# PWR.net
KiCad netlist of a schematic drawn in Altium Designer
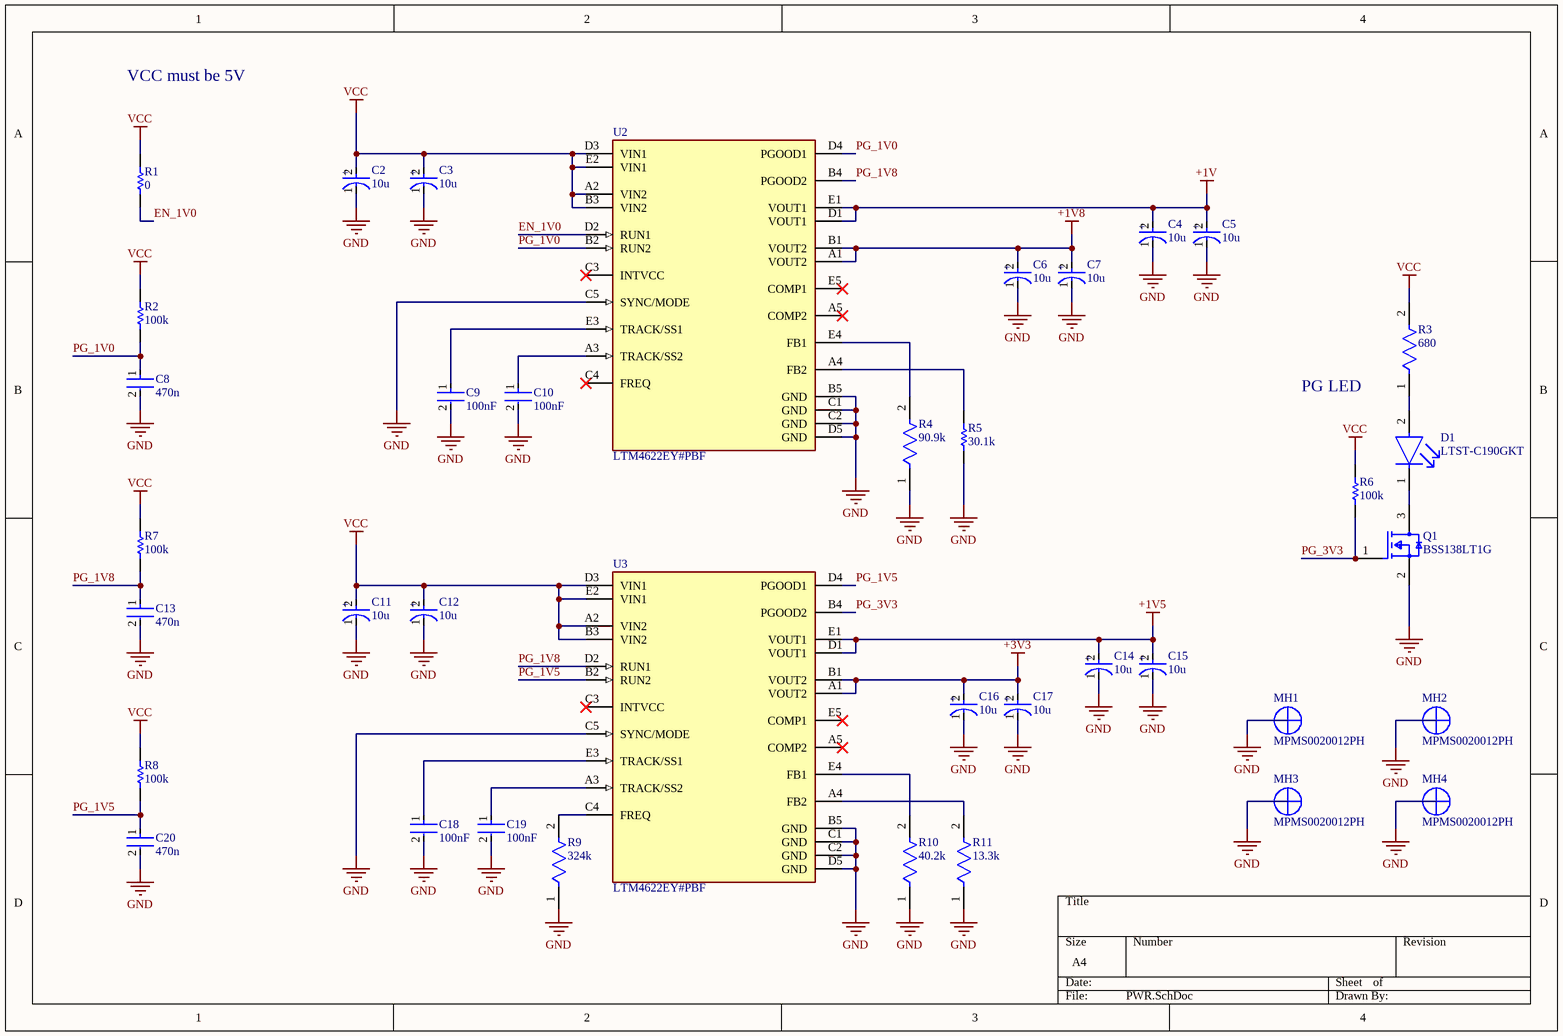
[diagram p0: PWR.SchDoc]

(export (version "E")
  (design (tool "Eeschema 10.0.6"))
  (components
    (comp (ref "C2")
      (value "10u")
      (footprint "FP-TAJB-MFG")
      (description "10uF 25V  ±10% 2.5Ω 1210  SMD Tantalum Capacitor")
      (fields (field (name "TOLERANCE") "10%"))
      (libsource (lib "Altium Content Vault") (part "203bc49f2ac43e59fd269a8c329ed05"))
    )
    (comp (ref "C3")
      (value "10u")
      (footprint "FP-TAJB-MFG")
      (description "10uF 25V  ±10% 2.5Ω 1210  SMD Tantalum Capacitor")
      (fields (field (name "TOLERANCE") "10%"))
      (libsource (lib "Altium Content Vault") (part "203bc49f2ac43e59fd269a8c329ed05"))
    )
    (comp (ref "C4")
      (value "10u")
      (footprint "FP-TAJA-MFG")
      (description "10uF 10V  ±10% 3Ω 1206  SMD Tantalum Capacitor")
      (fields (field (name "TOLERANCE") "10%") (field (name "VOLTAGE") "10V"))
      (libsource (lib "Altium Content Vault") (part "203bc49f2ac43e59fd269a8c329ed05"))
    )
    (comp (ref "C5")
      (value "10u")
      (footprint "FP-TAJA-MFG")
      (description "10uF 10V  ±10% 3Ω 1206  SMD Tantalum Capacitor")
      (fields (field (name "TOLERANCE") "10%") (field (name "VOLTAGE") "10V"))
      (libsource (lib "Altium Content Vault") (part "203bc49f2ac43e59fd269a8c329ed05"))
    )
    (comp (ref "C6")
      (value "10u")
      (footprint "FP-TAJA-MFG")
      (description "10uF 10V  ±10% 3Ω 1206  SMD Tantalum Capacitor")
      (fields (field (name "TOLERANCE") "10%") (field (name "VOLTAGE") "10V"))
      (libsource (lib "Altium Content Vault") (part "203bc49f2ac43e59fd269a8c329ed05"))
    )
    (comp (ref "C7")
      (value "10u")
      (footprint "FP-TAJA-MFG")
      (description "10uF 10V  ±10% 3Ω 1206  SMD Tantalum Capacitor")
      (fields (field (name "TOLERANCE") "10%") (field (name "VOLTAGE") "10V"))
      (libsource (lib "Altium Content Vault") (part "203bc49f2ac43e59fd269a8c329ed05"))
    )
    (comp (ref "C8")
      (value "470n")
      (footprint "FP-C0603C-CF-MFG")
      (description "CAP CER 0.47UF 16V X7R 0603")
      (fields (field (name "TOLERANCE") "0.1") (field (name "MANUFACTURER PART NUMBER") "C0603C474K4RACTU"))
      (libsource (lib "Altium Content Vault") (part "b4654b650e69147ec39a6b967a45e02"))
    )
    (comp (ref "C9")
      (value "100nF")
      (footprint "FP-CC0603-DA-MFG")
      (description "CAP CER 0.1UF 50V X7R 0603")
      (fields (field (name "MANUFACTURER") "YAGEO") (field (name "VOLTAGE") "50 V"))
      (libsource (lib "Altium Content Vault") (part "11868f565c42a9108669ba33697ecf6"))
    )
    (comp (ref "C10")
      (value "100nF")
      (footprint "FP-CC0603-DA-MFG")
      (description "CAP CER 0.1UF 50V X7R 0603")
      (fields (field (name "MANUFACTURER") "YAGEO") (field (name "VOLTAGE") "50 V"))
      (libsource (lib "Altium Content Vault") (part "11868f565c42a9108669ba33697ecf6"))
    )
    (comp (ref "C11")
      (value "10u")
      (footprint "FP-TAJB-MFG")
      (description "10uF 25V  ±10% 2.5Ω 1210  SMD Tantalum Capacitor")
      (fields (field (name "TOLERANCE") "10%"))
      (libsource (lib "Altium Content Vault") (part "203bc49f2ac43e59fd269a8c329ed05"))
    )
    (comp (ref "C12")
      (value "10u")
      (footprint "FP-TAJB-MFG")
      (description "10uF 25V  ±10% 2.5Ω 1210  SMD Tantalum Capacitor")
      (fields (field (name "TOLERANCE") "10%"))
      (libsource (lib "Altium Content Vault") (part "203bc49f2ac43e59fd269a8c329ed05"))
    )
    (comp (ref "C13")
      (value "470n")
      (footprint "FP-C0603C-CF-MFG")
      (description "CAP CER 0.47UF 16V X7R 0603")
      (fields (field (name "TOLERANCE") "0.1") (field (name "MANUFACTURER PART NUMBER") "C0603C474K4RACTU"))
      (libsource (lib "Altium Content Vault") (part "b4654b650e69147ec39a6b967a45e02"))
    )
    (comp (ref "C14")
      (value "10u")
      (footprint "FP-TAJA-MFG")
      (description "10uF 10V  ±10% 3Ω 1206  SMD Tantalum Capacitor")
      (fields (field (name "TOLERANCE") "10%") (field (name "VOLTAGE") "10V"))
      (libsource (lib "Altium Content Vault") (part "203bc49f2ac43e59fd269a8c329ed05"))
    )
    (comp (ref "C15")
      (value "10u")
      (footprint "FP-TAJA-MFG")
      (description "10uF 10V  ±10% 3Ω 1206  SMD Tantalum Capacitor")
      (fields (field (name "TOLERANCE") "10%") (field (name "VOLTAGE") "10V"))
      (libsource (lib "Altium Content Vault") (part "203bc49f2ac43e59fd269a8c329ed05"))
    )
    (comp (ref "C16")
      (value "10u")
      (footprint "FP-TAJA-MFG")
      (description "10uF 10V  ±10% 3Ω 1206  SMD Tantalum Capacitor")
      (fields (field (name "TOLERANCE") "10%") (field (name "VOLTAGE") "10V"))
      (libsource (lib "Altium Content Vault") (part "203bc49f2ac43e59fd269a8c329ed05"))
    )
    (comp (ref "C17")
      (value "10u")
      (footprint "FP-TAJA-MFG")
      (description "10uF 10V  ±10% 3Ω 1206  SMD Tantalum Capacitor")
      (fields (field (name "TOLERANCE") "10%") (field (name "VOLTAGE") "10V"))
      (libsource (lib "Altium Content Vault") (part "203bc49f2ac43e59fd269a8c329ed05"))
    )
    (comp (ref "C18")
      (value "100nF")
      (footprint "FP-CC0603-DA-MFG")
      (description "CAP CER 0.1UF 50V X7R 0603")
      (fields (field (name "MANUFACTURER") "YAGEO") (field (name "VOLTAGE") "50 V"))
      (libsource (lib "Altium Content Vault") (part "11868f565c42a9108669ba33697ecf6"))
    )
    (comp (ref "C19")
      (value "100nF")
      (footprint "FP-CC0603-DA-MFG")
      (description "CAP CER 0.1UF 50V X7R 0603")
      (fields (field (name "MANUFACTURER") "YAGEO") (field (name "VOLTAGE") "50 V"))
      (libsource (lib "Altium Content Vault") (part "11868f565c42a9108669ba33697ecf6"))
    )
    (comp (ref "C20")
      (value "470n")
      (footprint "FP-C0603C-CF-MFG")
      (description "CAP CER 0.47UF 16V X7R 0603")
      (fields (field (name "TOLERANCE") "0.1") (field (name "MANUFACTURER PART NUMBER") "C0603C474K4RACTU"))
      (libsource (lib "Altium Content Vault") (part "b4654b650e69147ec39a6b967a45e02"))
    )
    (comp (ref "D1")
      (value "LTST-C190GKT")
      (footprint "FP-LTST-C190GKT-MFG")
      (description "LED GREEN CLEAR CHIP SMD")
      (fields (field (name "VOLTAGE") "2V"))
      (libsource (lib "Altium Content Vault") (part "8706943c75ba83719d021d2fdc84c58"))
    )
    (comp (ref "MH1")
      (value "MPMS0020012PH")
      (footprint "BF-MPMS0020012PH")
      (description "Copper Pillar, M2 Screw")
      (fields (field (name "MANUFACTURER") "B&F Fastener Supply"))
      (libsource (lib "AkiPreamp") (part "BF-MPMS0020012PH"))
    )
    (comp (ref "MH2")
      (value "MPMS0020012PH")
      (footprint "BF-MPMS0020012PH")
      (description "Copper Pillar, M2 Screw")
      (fields (field (name "MANUFACTURER") "B&F Fastener Supply"))
      (libsource (lib "AkiPreamp") (part "BF-MPMS0020012PH"))
    )
    (comp (ref "MH3")
      (value "MPMS0020012PH")
      (footprint "BF-MPMS0020012PH")
      (description "Copper Pillar, M2 Screw")
      (fields (field (name "MANUFACTURER") "B&F Fastener Supply"))
      (libsource (lib "AkiPreamp") (part "BF-MPMS0020012PH"))
    )
    (comp (ref "MH4")
      (value "MPMS0020012PH")
      (footprint "BF-MPMS0020012PH")
      (description "Copper Pillar, M2 Screw")
      (fields (field (name "MANUFACTURER") "B&F Fastener Supply"))
      (libsource (lib "AkiPreamp") (part "BF-MPMS0020012PH"))
    )
    (comp (ref "Q1")
      (value "BSS138LT1G")
      (footprint "FP-318-MFG")
      (libsource (lib "Altium Content Vault") (part "0a9ea7c96deaaede766a5b531c28de0"))
    )
    (comp (ref "R1")
      (value "0")
      (footprint "RESC1608X55X25ML10T15")
      (description "Chip Resistor, 0 Ohm, +/- 5%, 0.1 W, -55 to 155 degC, 0603 (1608 Metric), RoHS, Tape and Reel")
      (fields (field (name "TOLERANCE") "5%") (field (name "MANUFACTURER") "Yageo"))
      (libsource (lib "Altium Content Vault") (part "RES-2"))
    )
    (comp (ref "R2")
      (value "100k")
      (footprint "RESC3116X65X40ML10T20")
      (description "Chip Resistor, 100 KOhm, +/- 1%, 0.25 W, -55 to 155 degC, 1206 (3216 Metric), RoHS, Tape and Reel")
      (fields (field (name "TOLERANCE") "1%") (field (name "MANUFACTURER") "Yageo"))
      (libsource (lib "Altium Content Vault") (part "RES-2"))
    )
    (comp (ref "R3")
      (value "680")
      (footprint "FP-RT0603-MFG")
      (description "RES SMD 680 OHM 0.1% 1/10W 0603")
      (fields
        (field (name "TOLERANCE") "0.001")
        (field (name "OCTOPART") "https://octopart.com/rt0603bre07680rl-yageo-1284352")
      )
      (libsource (lib "Altium Content Vault") (part "1029c3af85768c4190bb7ad29bc67b5"))
    )
    (comp (ref "R4")
      (value "90.9k")
      (footprint "FP-RT0603-MFG")
      (description "RES 90.9K OHM 1/10W .1% SMD 0603")
      (fields
        (field (name "MANUFACTURER PART NUMBER") "RT0603BRD0790K9L")
        (field (name "OCTOPART") "https://octopart.com/rt0603brd0790k9l-yageo-1479181")
      )
      (libsource (lib "Altium Content Vault") (part "1029c3af85768c4190bb7ad29bc67b5"))
    )
    (comp (ref "R5")
      (value "30.1k")
      (footprint "RESC0603(1608)_N")
      (description "30K1 0.1W 1% 0603 (1608 Metric)  SMD")
      (fields (field (name "TOLERANCE") "1 %") (field (name "POWER") "0.1 W"))
      (libsource (lib "Altium Content Vault") (part "RES"))
    )
    (comp (ref "R6")
      (value "100k")
      (footprint "RESC3116X65X40ML10T20")
      (description "Chip Resistor, 100 KOhm, +/- 1%, 0.25 W, -55 to 155 degC, 1206 (3216 Metric), RoHS, Tape and Reel")
      (fields (field (name "TOLERANCE") "1%") (field (name "MANUFACTURER") "Yageo"))
      (libsource (lib "Altium Content Vault") (part "RES-2"))
    )
    (comp (ref "R7")
      (value "100k")
      (footprint "RESC3116X65X40ML10T20")
      (description "Chip Resistor, 100 KOhm, +/- 1%, 0.25 W, -55 to 155 degC, 1206 (3216 Metric), RoHS, Tape and Reel")
      (fields (field (name "TOLERANCE") "1%") (field (name "MANUFACTURER") "Yageo"))
      (libsource (lib "Altium Content Vault") (part "RES-2"))
    )
    (comp (ref "R8")
      (value "100k")
      (footprint "RESC3116X65X40ML10T20")
      (description "Chip Resistor, 100 KOhm, +/- 1%, 0.25 W, -55 to 155 degC, 1206 (3216 Metric), RoHS, Tape and Reel")
      (fields (field (name "TOLERANCE") "1%") (field (name "MANUFACTURER") "Yageo"))
      (libsource (lib "Altium Content Vault") (part "RES-2"))
    )
    (comp (ref "R9")
      (value "324k")
      (footprint "FP-RT0603-MFG")
      (description "RES SMD 324K OHM 1% 1/10W 0603")
      (fields (field (name "TOLERANCE") "0.01") (field (name "MANUFACTURER") "Yageo"))
      (libsource (lib "Altium Content Vault") (part "1029c3af85768c4190bb7ad29bc67b5"))
    )
    (comp (ref "R10")
      (value "40.2k")
      (footprint "FP-RT0603-MFG")
      (description "RES SMD 40.2K OHM 0.1% 1/10W")
      (fields
        (field (name "OCTOPART") "https://octopart.com/rt0603brd0740k2l-yageo-1425510")
        (field (name "MANUFACTURER") "Yageo")
      )
      (libsource (lib "Altium Content Vault") (part "1029c3af85768c4190bb7ad29bc67b5"))
    )
    (comp (ref "R11")
      (value "13.3k")
      (footprint "FP-RT0603-MFG")
      (description "RES 13.3KOHM 1/10W .1% SMD 0603")
      (fields (field (name "MANUFACTURER") "Yageo") (field (name "TOLERANCE") "0.001"))
      (libsource (lib "Altium Content Vault") (part "1029c3af85768c4190bb7ad29bc67b5"))
    )
    (comp (ref "U2")
      (value "LTM4622EY#PBF")
      (footprint "FP-BGA-25-05-08-1502-MFG")
      (description "DC DC CNVRTR 0.6-5.5V 0.6-5.5V")
      (libsource (lib "Altium Content Vault") (part "dc5f1d4b10e399b82fc0b0a9395dfb6"))
    )
    (comp (ref "U3")
      (value "LTM4622EY#PBF")
      (footprint "FP-BGA-25-05-08-1502-MFG")
      (description "DC DC CNVRTR 0.6-5.5V 0.6-5.5V")
      (libsource (lib "Altium Content Vault") (part "dc5f1d4b10e399b82fc0b0a9395dfb6"))
    )
  )
  (nets
    (net (code "1") (name "+1V") (class "Default")
      (node (ref "C4") (pin "2") (pinfunction "A_2") (pintype "passive"))
      (node (ref "C5") (pin "2") (pinfunction "A_2") (pintype "passive"))
      (node (ref "U2") (pin "D1") (pinfunction "VOUT1_D1") (pintype "power_in"))
      (node (ref "U2") (pin "E1") (pinfunction "VOUT1_E1") (pintype "power_in"))
    )
    (net (code "2") (name "+1V5") (class "Default")
      (node (ref "C14") (pin "2") (pinfunction "A_2") (pintype "passive"))
      (node (ref "C15") (pin "2") (pinfunction "A_2") (pintype "passive"))
      (node (ref "U3") (pin "D1") (pinfunction "VOUT1_D1") (pintype "power_in"))
      (node (ref "U3") (pin "E1") (pinfunction "VOUT1_E1") (pintype "power_in"))
    )
    (net (code "3") (name "+1V8") (class "Default")
      (node (ref "C6") (pin "2") (pinfunction "A_2") (pintype "passive"))
      (node (ref "C7") (pin "2") (pinfunction "A_2") (pintype "passive"))
      (node (ref "U2") (pin "A1") (pinfunction "VOUT2_A1") (pintype "power_in"))
      (node (ref "U2") (pin "B1") (pinfunction "VOUT2_B1") (pintype "power_in"))
    )
    (net (code "4") (name "+3V3") (class "Default")
      (node (ref "C16") (pin "2") (pinfunction "A_2") (pintype "passive"))
      (node (ref "C17") (pin "2") (pinfunction "A_2") (pintype "passive"))
      (node (ref "U3") (pin "A1") (pinfunction "VOUT2_A1") (pintype "power_in"))
      (node (ref "U3") (pin "B1") (pinfunction "VOUT2_B1") (pintype "power_in"))
    )
    (net (code "5") (name "/EN_1V0") (class "Default")
      (node (ref "R1") (pin "1") (pinfunction "1_1") (pintype "passive"))
      (node (ref "U2") (pin "D2") (pinfunction "RUN1_D2") (pintype "input"))
    )
    (net (code "6") (name "/PG_1V0") (class "Default")
      (node (ref "C8") (pin "1") (pinfunction "1_1") (pintype "passive"))
      (node (ref "R2") (pin "1") (pinfunction "1_1") (pintype "passive"))
      (node (ref "U2") (pin "B2") (pinfunction "RUN2_B2") (pintype "input"))
      (node (ref "U2") (pin "D4") (pinfunction "PGOOD1_D4") (pintype "open_collector"))
    )
    (net (code "7") (name "/PG_1V5") (class "Default")
      (node (ref "C20") (pin "1") (pinfunction "1_1") (pintype "passive"))
      (node (ref "R8") (pin "1") (pinfunction "1_1") (pintype "passive"))
      (node (ref "U3") (pin "B2") (pinfunction "RUN2_B2") (pintype "input"))
      (node (ref "U3") (pin "D4") (pinfunction "PGOOD1_D4") (pintype "open_collector"))
    )
    (net (code "8") (name "/PG_1V8") (class "Default")
      (node (ref "C13") (pin "1") (pinfunction "1_1") (pintype "passive"))
      (node (ref "R7") (pin "1") (pinfunction "1_1") (pintype "passive"))
      (node (ref "U2") (pin "B4") (pinfunction "PGOOD2_B4") (pintype "open_collector"))
      (node (ref "U3") (pin "D2") (pinfunction "RUN1_D2") (pintype "input"))
    )
    (net (code "9") (name "/PG_3V3") (class "Default")
      (node (ref "Q1") (pin "1") (pinfunction "G_1") (pintype "passive"))
      (node (ref "R6") (pin "1") (pinfunction "1_1") (pintype "passive"))
      (node (ref "U3") (pin "B4") (pinfunction "PGOOD2_B4") (pintype "open_collector"))
    )
    (net (code "10") (name "GND") (class "Default")
      (node (ref "C10") (pin "2") (pinfunction "2_2") (pintype "passive"))
      (node (ref "C11") (pin "1") (pinfunction "C_1") (pintype "passive"))
      (node (ref "C12") (pin "1") (pinfunction "C_1") (pintype "passive"))
      (node (ref "C13") (pin "2") (pinfunction "2_2") (pintype "passive"))
      (node (ref "C14") (pin "1") (pinfunction "C_1") (pintype "passive"))
      (node (ref "C15") (pin "1") (pinfunction "C_1") (pintype "passive"))
      (node (ref "C16") (pin "1") (pinfunction "C_1") (pintype "passive"))
      (node (ref "C17") (pin "1") (pinfunction "C_1") (pintype "passive"))
      (node (ref "C18") (pin "2") (pinfunction "2_2") (pintype "passive"))
      (node (ref "C19") (pin "2") (pinfunction "2_2") (pintype "passive"))
      (node (ref "C2") (pin "1") (pinfunction "C_1") (pintype "passive"))
      (node (ref "C20") (pin "2") (pinfunction "2_2") (pintype "passive"))
      (node (ref "C3") (pin "1") (pinfunction "C_1") (pintype "passive"))
      (node (ref "C4") (pin "1") (pinfunction "C_1") (pintype "passive"))
      (node (ref "C5") (pin "1") (pinfunction "C_1") (pintype "passive"))
      (node (ref "C6") (pin "1") (pinfunction "C_1") (pintype "passive"))
      (node (ref "C7") (pin "1") (pinfunction "C_1") (pintype "passive"))
      (node (ref "C8") (pin "2") (pinfunction "2_2") (pintype "passive"))
      (node (ref "C9") (pin "2") (pinfunction "2_2") (pintype "passive"))
      (node (ref "MH1") (pin "1") (pinfunction "1_1") (pintype "passive"))
      (node (ref "MH2") (pin "1") (pinfunction "1_1") (pintype "passive"))
      (node (ref "MH3") (pin "1") (pinfunction "1_1") (pintype "passive"))
      (node (ref "MH4") (pin "1") (pinfunction "1_1") (pintype "passive"))
      (node (ref "Q1") (pin "2") (pinfunction "S_2") (pintype "passive"))
      (node (ref "R10") (pin "1") (pinfunction "1_1") (pintype "passive"))
      (node (ref "R11") (pin "1") (pinfunction "1_1") (pintype "passive"))
      (node (ref "R4") (pin "1") (pinfunction "1_1") (pintype "passive"))
      (node (ref "R5") (pin "1") (pinfunction "1_1") (pintype "passive"))
      (node (ref "R9") (pin "1") (pinfunction "1_1") (pintype "passive"))
      (node (ref "U2") (pin "B5") (pinfunction "GND_B5") (pintype "power_in"))
      (node (ref "U2") (pin "C1") (pinfunction "GND_C1") (pintype "power_in"))
      (node (ref "U2") (pin "C2") (pinfunction "GND_C2") (pintype "power_in"))
      (node (ref "U2") (pin "C5") (pinfunction "SYNC/MODE_C5") (pintype "input"))
      (node (ref "U2") (pin "D5") (pinfunction "GND_D5") (pintype "power_in"))
      (node (ref "U3") (pin "B5") (pinfunction "GND_B5") (pintype "power_in"))
      (node (ref "U3") (pin "C1") (pinfunction "GND_C1") (pintype "power_in"))
      (node (ref "U3") (pin "C2") (pinfunction "GND_C2") (pintype "power_in"))
      (node (ref "U3") (pin "C5") (pinfunction "SYNC/MODE_C5") (pintype "input"))
      (node (ref "U3") (pin "D5") (pinfunction "GND_D5") (pintype "power_in"))
    )
    (net (code "11") (name "Net-(D1-A)") (class "Default")
      (node (ref "D1") (pin "2") (pinfunction "A_2") (pintype "passive"))
      (node (ref "R3") (pin "1") (pinfunction "1_1") (pintype "passive"))
    )
    (net (code "12") (name "Net-(D1-C)") (class "Default")
      (node (ref "D1") (pin "1") (pinfunction "C_1") (pintype "passive"))
      (node (ref "Q1") (pin "3") (pinfunction "D_3") (pintype "passive"))
    )
    (net (code "13") (name "Net-(U2-FB1)") (class "Default")
      (node (ref "R4") (pin "2") (pinfunction "2_2") (pintype "passive"))
      (node (ref "U2") (pin "E4") (pinfunction "FB1_E4") (pintype "passive"))
    )
    (net (code "14") (name "Net-(U2-FB2)") (class "Default")
      (node (ref "R5") (pin "2") (pinfunction "2_2") (pintype "passive"))
      (node (ref "U2") (pin "A4") (pinfunction "FB2_A4") (pintype "passive"))
    )
    (net (code "15") (name "Net-(U2-TRACK{slash}SS1)") (class "Default")
      (node (ref "C9") (pin "1") (pinfunction "1_1") (pintype "passive"))
      (node (ref "U2") (pin "E3") (pinfunction "TRACK/SS1_E3") (pintype "input"))
    )
    (net (code "16") (name "Net-(U2-TRACK{slash}SS2)") (class "Default")
      (node (ref "C10") (pin "1") (pinfunction "1_1") (pintype "passive"))
      (node (ref "U2") (pin "A3") (pinfunction "TRACK/SS2_A3") (pintype "input"))
    )
    (net (code "17") (name "Net-(U3-FB1)") (class "Default")
      (node (ref "R10") (pin "2") (pinfunction "2_2") (pintype "passive"))
      (node (ref "U3") (pin "E4") (pinfunction "FB1_E4") (pintype "passive"))
    )
    (net (code "18") (name "Net-(U3-FB2)") (class "Default")
      (node (ref "R11") (pin "2") (pinfunction "2_2") (pintype "passive"))
      (node (ref "U3") (pin "A4") (pinfunction "FB2_A4") (pintype "passive"))
    )
    (net (code "19") (name "Net-(U3-FREQ)") (class "Default")
      (node (ref "R9") (pin "2") (pinfunction "2_2") (pintype "passive"))
      (node (ref "U3") (pin "C4") (pinfunction "FREQ_C4") (pintype "passive"))
    )
    (net (code "20") (name "Net-(U3-TRACK{slash}SS1)") (class "Default")
      (node (ref "C18") (pin "1") (pinfunction "1_1") (pintype "passive"))
      (node (ref "U3") (pin "E3") (pinfunction "TRACK/SS1_E3") (pintype "input"))
    )
    (net (code "21") (name "Net-(U3-TRACK{slash}SS2)") (class "Default")
      (node (ref "C19") (pin "1") (pinfunction "1_1") (pintype "passive"))
      (node (ref "U3") (pin "A3") (pinfunction "TRACK/SS2_A3") (pintype "input"))
    )
    (net (code "22") (name "VCC") (class "Default")
      (node (ref "C11") (pin "2") (pinfunction "A_2") (pintype "passive"))
      (node (ref "C12") (pin "2") (pinfunction "A_2") (pintype "passive"))
      (node (ref "C2") (pin "2") (pinfunction "A_2") (pintype "passive"))
      (node (ref "C3") (pin "2") (pinfunction "A_2") (pintype "passive"))
      (node (ref "R1") (pin "2") (pinfunction "2_2") (pintype "passive"))
      (node (ref "R2") (pin "2") (pinfunction "2_2") (pintype "passive"))
      (node (ref "R3") (pin "2") (pinfunction "2_2") (pintype "passive"))
      (node (ref "R6") (pin "2") (pinfunction "2_2") (pintype "passive"))
      (node (ref "R7") (pin "2") (pinfunction "2_2") (pintype "passive"))
      (node (ref "R8") (pin "2") (pinfunction "2_2") (pintype "passive"))
      (node (ref "U2") (pin "A2") (pinfunction "VIN2_A2") (pintype "power_in"))
      (node (ref "U2") (pin "B3") (pinfunction "VIN2_B3") (pintype "power_in"))
      (node (ref "U2") (pin "D3") (pinfunction "VIN1_D3") (pintype "power_in"))
      (node (ref "U2") (pin "E2") (pinfunction "VIN1_E2") (pintype "power_in"))
      (node (ref "U3") (pin "A2") (pinfunction "VIN2_A2") (pintype "power_in"))
      (node (ref "U3") (pin "B3") (pinfunction "VIN2_B3") (pintype "power_in"))
      (node (ref "U3") (pin "D3") (pinfunction "VIN1_D3") (pintype "power_in"))
      (node (ref "U3") (pin "E2") (pinfunction "VIN1_E2") (pintype "power_in"))
    )
    (net (code "23") (name "unconnected-(U2-COMP1-PadE5)") (class "Default")
      (node (ref "U2") (pin "E5") (pinfunction "COMP1_E5") (pintype "passive+no_connect"))
    )
    (net (code "24") (name "unconnected-(U2-COMP2-PadA5)") (class "Default")
      (node (ref "U2") (pin "A5") (pinfunction "COMP2_A5") (pintype "passive+no_connect"))
    )
    (net (code "25") (name "unconnected-(U2-FREQ-PadC4)") (class "Default")
      (node (ref "U2") (pin "C4") (pinfunction "FREQ_C4") (pintype "passive+no_connect"))
    )
    (net (code "26") (name "unconnected-(U2-INTVCC-PadC3)") (class "Default")
      (node (ref "U2") (pin "C3") (pinfunction "INTVCC_C3") (pintype "passive+no_connect"))
    )
    (net (code "27") (name "unconnected-(U3-COMP1-PadE5)") (class "Default")
      (node (ref "U3") (pin "E5") (pinfunction "COMP1_E5") (pintype "passive+no_connect"))
    )
    (net (code "28") (name "unconnected-(U3-COMP2-PadA5)") (class "Default")
      (node (ref "U3") (pin "A5") (pinfunction "COMP2_A5") (pintype "passive+no_connect"))
    )
    (net (code "29") (name "unconnected-(U3-INTVCC-PadC3)") (class "Default")
      (node (ref "U3") (pin "C3") (pinfunction "INTVCC_C3") (pintype "passive+no_connect"))
    )
  )
)
